# 802_15_4_AT86RF231-chip.net
KiCad netlist of a schematic drawn in EAGLE
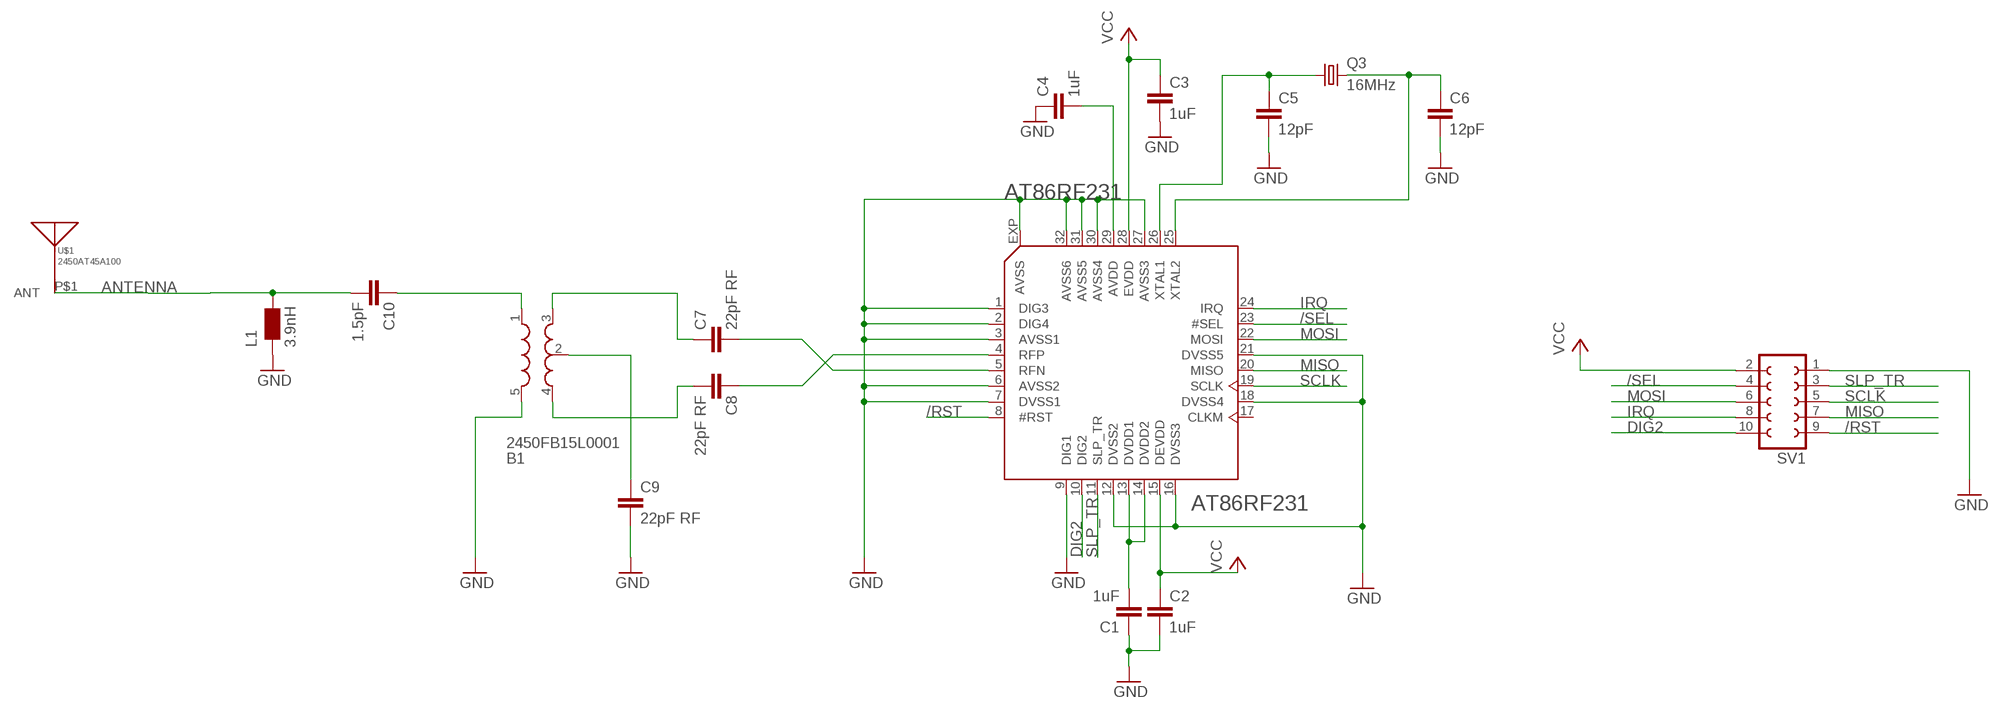
[diagram p0: schematic, sheet 1]

(export (version "E")
  (design (tool "Eeschema 10.0.6"))
  (components
    (comp (ref "AT86RF231")
      (value "AT86RF231")
      (footprint "eagle-import:QFN32")
      (libsource (lib "eagle-import") (part "AT86RF231"))
    )
    (comp (ref "B1")
      (value "2450FB15L0001")
      (footprint "eagle-import:BALUN")
      (libsource (lib "eagle-import") (part "BALUN0805"))
    )
    (comp (ref "C1")
      (value "1uF")
      (footprint "eagle-import:C0402K")
      (libsource (lib "eagle-import") (part "C-EUC0402K"))
    )
    (comp (ref "C2")
      (value "1uF")
      (footprint "eagle-import:C0402K")
      (libsource (lib "eagle-import") (part "C-EUC0402K"))
    )
    (comp (ref "C3")
      (value "1uF")
      (footprint "eagle-import:C0402K")
      (libsource (lib "eagle-import") (part "C-EUC0402K"))
    )
    (comp (ref "C4")
      (value "1uF")
      (footprint "eagle-import:C0402K")
      (libsource (lib "eagle-import") (part "C-EUC0402K"))
    )
    (comp (ref "C5")
      (value "12pF")
      (footprint "eagle-import:C0402K")
      (libsource (lib "eagle-import") (part "C-EUC0402K"))
    )
    (comp (ref "C6")
      (value "12pF")
      (footprint "eagle-import:C0402K")
      (libsource (lib "eagle-import") (part "C-EUC0402K"))
    )
    (comp (ref "C7")
      (value "22pF RF")
      (footprint "eagle-import:C0402K")
      (libsource (lib "eagle-import") (part "C-EUC0402K"))
    )
    (comp (ref "C8")
      (value "22pF RF")
      (footprint "eagle-import:C0402K")
      (libsource (lib "eagle-import") (part "C-EUC0402K"))
    )
    (comp (ref "C9")
      (value "22pF RF")
      (footprint "eagle-import:C0402K")
      (libsource (lib "eagle-import") (part "C-EUC0402K"))
    )
    (comp (ref "C10")
      (value "1.5pF")
      (footprint "eagle-import:C0402K")
      (libsource (lib "eagle-import") (part "C-EUC0402K"))
    )
    (comp (ref "L1")
      (value "3.9nH")
      (footprint "eagle-import:0402")
      (libsource (lib "eagle-import") (part "WE-CBF_0402"))
    )
    (comp (ref "Q3")
      (value "16MHz")
      (footprint "eagle-import:CTS406")
      (libsource (lib "eagle-import") (part "CRYSTALCTS406"))
    )
    (comp (ref "SV1")
      (value "FE05-2")
      (footprint "eagle-import:FE05-2")
      (libsource (lib "eagle-import") (part "FE05-2"))
    )
    (comp (ref "U$1")
      (value "2450AT45A100")
      (footprint "eagle-import:2450AT45A100")
      (libsource (lib "eagle-import") (part "2450AT45A100"))
    )
  )
  (nets
    (net (code "1") (name "/ANTENNA") (class "Default")
      (node (ref "C10") (pin "2") (pinfunction "2_2") (pintype "passive"))
      (node (ref "L1") (pin "2") (pinfunction "2_2") (pintype "passive"))
      (node (ref "U$1") (pin "P$1") (pinfunction "ANT_P$1") (pintype "output"))
    )
    (net (code "2") (name "/DIG2") (class "Default")
      (node (ref "AT86RF231") (pin "10") (pinfunction "DIG2_10") (pintype "power_in"))
      (node (ref "SV1") (pin "10") (pinfunction "10_10") (pintype "passive"))
    )
    (net (code "3") (name "/IRQ") (class "Default")
      (node (ref "AT86RF231") (pin "24") (pinfunction "IRQ_24") (pintype "output"))
      (node (ref "SV1") (pin "8") (pinfunction "8_8") (pintype "passive"))
    )
    (net (code "4") (name "/MISO") (class "Default")
      (node (ref "AT86RF231") (pin "20") (pinfunction "MISO_20") (pintype "output"))
      (node (ref "SV1") (pin "7") (pinfunction "7_7") (pintype "passive"))
    )
    (net (code "5") (name "/MOSI") (class "Default")
      (node (ref "AT86RF231") (pin "22") (pinfunction "MOSI_22") (pintype "input"))
      (node (ref "SV1") (pin "6") (pinfunction "6_6") (pintype "passive"))
    )
    (net (code "6") (name "/SCLK") (class "Default")
      (node (ref "AT86RF231") (pin "19") (pinfunction "SCLK_19") (pintype "input"))
      (node (ref "SV1") (pin "5") (pinfunction "5_5") (pintype "passive"))
    )
    (net (code "7") (name "/SLP_TR") (class "Default")
      (node (ref "AT86RF231") (pin "11") (pinfunction "SLP_TR_11") (pintype "input"))
      (node (ref "SV1") (pin "3") (pinfunction "3_3") (pintype "passive"))
    )
    (net (code "8") (name "/{slash}RST") (class "Default")
      (node (ref "AT86RF231") (pin "8") (pinfunction "#RST_8") (pintype "input"))
      (node (ref "SV1") (pin "9") (pinfunction "9_9") (pintype "passive"))
    )
    (net (code "9") (name "/{slash}SEL") (class "Default")
      (node (ref "AT86RF231") (pin "23") (pinfunction "#SEL_23") (pintype "input"))
      (node (ref "SV1") (pin "4") (pinfunction "4_4") (pintype "passive"))
    )
    (net (code "10") (name "GND") (class "Default")
      (node (ref "AT86RF231") (pin "1") (pinfunction "DIG3_1") (pintype "power_in"))
      (node (ref "AT86RF231") (pin "12") (pinfunction "DVSS2_12") (pintype "power_in"))
      (node (ref "AT86RF231") (pin "16") (pinfunction "DVSS3_16") (pintype "power_in"))
      (node (ref "AT86RF231") (pin "18") (pinfunction "DVSS4_18") (pintype "power_in"))
      (node (ref "AT86RF231") (pin "2") (pinfunction "DIG4_2") (pintype "power_in"))
      (node (ref "AT86RF231") (pin "21") (pinfunction "DVSS5_21") (pintype "power_in"))
      (node (ref "AT86RF231") (pin "27") (pinfunction "AVSS3_27") (pintype "power_in"))
      (node (ref "AT86RF231") (pin "3") (pinfunction "AVSS1_3") (pintype "power_in"))
      (node (ref "AT86RF231") (pin "30") (pinfunction "AVSS4_30") (pintype "power_in"))
      (node (ref "AT86RF231") (pin "31") (pinfunction "AVSS5_31") (pintype "power_in"))
      (node (ref "AT86RF231") (pin "32") (pinfunction "AVSS6_32") (pintype "bidirectional"))
      (node (ref "AT86RF231") (pin "6") (pinfunction "AVSS2_6") (pintype "power_in"))
      (node (ref "AT86RF231") (pin "7") (pinfunction "DVSS1_7") (pintype "power_in"))
      (node (ref "AT86RF231") (pin "9") (pinfunction "DIG1_9") (pintype "power_in"))
      (node (ref "AT86RF231") (pin "EXP") (pinfunction "AVSS_EXP") (pintype "power_in"))
      (node (ref "B1") (pin "5") (pinfunction "GND_5") (pintype "bidirectional"))
      (node (ref "C1") (pin "1") (pinfunction "1_1") (pintype "passive"))
      (node (ref "C2") (pin "2") (pinfunction "2_2") (pintype "passive"))
      (node (ref "C3") (pin "2") (pinfunction "2_2") (pintype "passive"))
      (node (ref "C4") (pin "1") (pinfunction "1_1") (pintype "passive"))
      (node (ref "C5") (pin "2") (pinfunction "2_2") (pintype "passive"))
      (node (ref "C6") (pin "2") (pinfunction "2_2") (pintype "passive"))
      (node (ref "C9") (pin "2") (pinfunction "2_2") (pintype "passive"))
      (node (ref "L1") (pin "1") (pinfunction "1_1") (pintype "passive"))
      (node (ref "SV1") (pin "1") (pinfunction "1_1") (pintype "passive"))
    )
    (net (code "11") (name "Net-(AT86RF231-AVDD)") (class "Default")
      (node (ref "AT86RF231") (pin "29") (pinfunction "AVDD_29") (pintype "power_in"))
      (node (ref "C4") (pin "2") (pinfunction "2_2") (pintype "passive"))
    )
    (net (code "12") (name "Net-(AT86RF231-DVDD1)") (class "Default")
      (node (ref "AT86RF231") (pin "13") (pinfunction "DVDD1_13") (pintype "power_in"))
      (node (ref "AT86RF231") (pin "14") (pinfunction "DVDD2_14") (pintype "power_in"))
      (node (ref "C1") (pin "2") (pinfunction "2_2") (pintype "passive"))
    )
    (net (code "13") (name "Net-(AT86RF231-RFN)") (class "Default")
      (node (ref "AT86RF231") (pin "5") (pinfunction "RFN_5") (pintype "bidirectional"))
      (node (ref "C7") (pin "2") (pinfunction "2_2") (pintype "passive"))
    )
    (net (code "14") (name "Net-(AT86RF231-RFP)") (class "Default")
      (node (ref "AT86RF231") (pin "4") (pinfunction "RFP_4") (pintype "bidirectional"))
      (node (ref "C8") (pin "1") (pinfunction "1_1") (pintype "passive"))
    )
    (net (code "15") (name "Net-(AT86RF231-XTAL1)") (class "Default")
      (node (ref "AT86RF231") (pin "26") (pinfunction "XTAL1_26") (pintype "input"))
      (node (ref "C5") (pin "1") (pinfunction "1_1") (pintype "passive"))
      (node (ref "Q3") (pin "1") (pinfunction "1_1") (pintype "passive"))
    )
    (net (code "16") (name "Net-(AT86RF231-XTAL2)") (class "Default")
      (node (ref "AT86RF231") (pin "25") (pinfunction "XTAL2_25") (pintype "bidirectional"))
      (node (ref "C6") (pin "1") (pinfunction "1_1") (pintype "passive"))
      (node (ref "Q3") (pin "3") (pinfunction "2_3") (pintype "passive"))
    )
    (net (code "17") (name "Net-(B1-GND-Pad2)") (class "Default")
      (node (ref "B1") (pin "2") (pinfunction "GND_2") (pintype "bidirectional"))
      (node (ref "C9") (pin "1") (pinfunction "1_1") (pintype "passive"))
    )
    (net (code "18") (name "Net-(B1-IN)") (class "Default")
      (node (ref "B1") (pin "1") (pinfunction "IN_1") (pintype "bidirectional"))
      (node (ref "C10") (pin "1") (pinfunction "1_1") (pintype "passive"))
    )
    (net (code "19") (name "Net-(B1-OUT1)") (class "Default")
      (node (ref "B1") (pin "3") (pinfunction "OUT1_3") (pintype "bidirectional"))
      (node (ref "C7") (pin "1") (pinfunction "1_1") (pintype "passive"))
    )
    (net (code "20") (name "Net-(B1-OUT2)") (class "Default")
      (node (ref "B1") (pin "4") (pinfunction "OUT2_4") (pintype "bidirectional"))
      (node (ref "C8") (pin "2") (pinfunction "2_2") (pintype "passive"))
    )
    (net (code "21") (name "VCC") (class "Default")
      (node (ref "AT86RF231") (pin "15") (pinfunction "DEVDD_15") (pintype "power_in"))
      (node (ref "AT86RF231") (pin "28") (pinfunction "EVDD_28") (pintype "power_in"))
      (node (ref "C2") (pin "1") (pinfunction "1_1") (pintype "passive"))
      (node (ref "C3") (pin "1") (pinfunction "1_1") (pintype "passive"))
      (node (ref "SV1") (pin "2") (pinfunction "2_2") (pintype "passive"))
    )
    (net (code "22") (name "unconnected-(AT86RF231-CLKM-Pad17)") (class "Default")
      (node (ref "AT86RF231") (pin "17") (pinfunction "CLKM_17") (pintype "output"))
    )
  )
)
